# MCU.net
KiCad netlist of a schematic drawn in Altium Designer
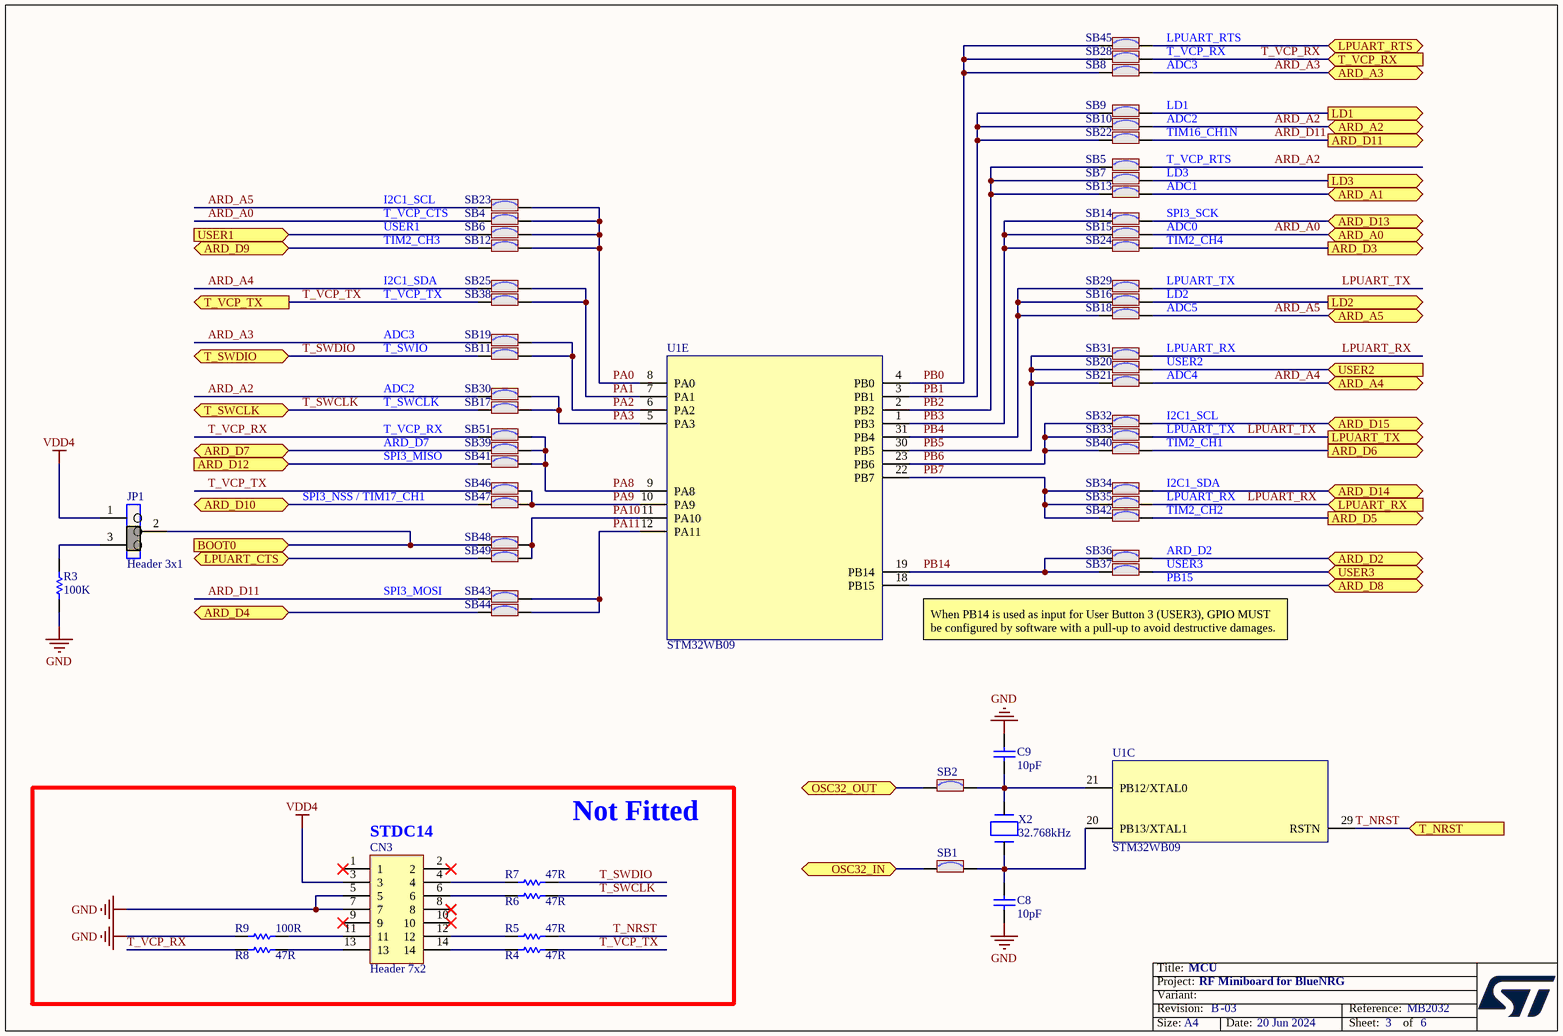
[diagram p0: MCU.SchDoc]

(export (version "E")
  (design (tool "Eeschema 10.0.6"))
  (components
    (comp (ref "C8")
      (value "10pF")
      (footprint "MCD_PARTS:C0402")
      (description "Capacitor, MLCC, 10pF, 50V, NPO, +/-5%, 0402, T=0.5mm")
      (fields (field (name "INTERNAL_PART_NUMBER") "MCD-00015") (field (name "MANUFACTURER") "YAGEO"))
      (libsource (lib "MCD_PARTS_database") (part "Capacitor"))
    )
    (comp (ref "C9")
      (value "10pF")
      (footprint "MCD_PARTS:C0402")
      (description "Capacitor, MLCC, 10pF, 50V, NPO, +/-5%, 0402, T=0.5mm")
      (fields (field (name "INTERNAL_PART_NUMBER") "MCD-00015") (field (name "MANUFACTURER") "YAGEO"))
      (libsource (lib "MCD_PARTS_database") (part "Capacitor"))
    )
    (comp (ref "CN3")
      (value "Header 7x2")
      (footprint "MCD_PARTS:CON_SAMTEC_FTSH-107-01-L-DV-K")
      (description "Header, 7x2, 1.27mm, VR, T=5.97mm, FTSH series STDC14 without Alignment Pin")
      (fields (field (name "INTERNAL_PART_NUMBER") "MCD-01531") (field (name "MANUFACTURER") "SAMTEC"))
      (libsource (lib "MCD_PARTS_database") (part "Header 7x2"))
    )
    (comp (ref "JP1")
      (value "Header 3x1")
      (footprint "CON_SAMTEC_TSW-103-07-F-S")
      (description "Header, 3x1, 2.54mm, VR, TH, T=5.84mm/2.54mm")
      (fields (field (name "INTERNAL_PART_NUMBER") "MCD-00685") (field (name "MANUFACTURER") "SAMTEC"))
      (libsource (lib "MCD_PARTS_database") (part "Jumper_Header 3x1 Fitted 2-3"))
    )
    (comp (ref "R3")
      (value "100K")
      (footprint "R0402")
      (description "Resistor, 100K, 0402, +/-1%, 1/16W")
      (fields (field (name "INTERNAL_PART_NUMBER") "MCD-00059") (field (name "MANUFACTURER") "YAGEO"))
      (libsource (lib "MCD_PARTS_database") (part "Resistor"))
    )
    (comp (ref "R4")
      (value "47R")
      (footprint "MCD_PARTS:R0402")
      (description "Resistor, 47R, 0402, +/-1%, 1/16W")
      (fields (field (name "INTERNAL_PART_NUMBER") "MCD-00481") (field (name "MANUFACTURER") "YAGEO"))
      (libsource (lib "MCD_PARTS_database") (part "Resistor"))
    )
    (comp (ref "R5")
      (value "47R")
      (footprint "MCD_PARTS:R0402")
      (description "Resistor, 47R, 0402, +/-1%, 1/16W")
      (fields (field (name "INTERNAL_PART_NUMBER") "MCD-00481") (field (name "MANUFACTURER") "YAGEO"))
      (libsource (lib "MCD_PARTS_database") (part "Resistor"))
    )
    (comp (ref "R6")
      (value "47R")
      (footprint "MCD_PARTS:R0402")
      (description "Resistor, 47R, 0402, +/-1%, 1/16W")
      (fields (field (name "INTERNAL_PART_NUMBER") "MCD-00481") (field (name "MANUFACTURER") "YAGEO"))
      (libsource (lib "MCD_PARTS_database") (part "Resistor"))
    )
    (comp (ref "R7")
      (value "47R")
      (footprint "MCD_PARTS:R0402")
      (description "Resistor, 47R, 0402, +/-1%, 1/16W")
      (fields (field (name "INTERNAL_PART_NUMBER") "MCD-00481") (field (name "MANUFACTURER") "YAGEO"))
      (libsource (lib "MCD_PARTS_database") (part "Resistor"))
    )
    (comp (ref "R8")
      (value "47R")
      (footprint "MCD_PARTS:R0402")
      (description "Resistor, 47R, 0402, +/-1%, 1/16W")
      (fields (field (name "INTERNAL_PART_NUMBER") "MCD-00481") (field (name "MANUFACTURER") "YAGEO"))
      (libsource (lib "MCD_PARTS_database") (part "Resistor"))
    )
    (comp (ref "R9")
      (value "100R")
      (footprint "MCD_PARTS:R0402")
      (description "Resistor, 100R, 0402, +/- 1%, 1/16W")
      (fields (field (name "INTERNAL_PART_NUMBER") "MCD-00067") (field (name "MANUFACTURER") "YAGEO"))
      (libsource (lib "MCD_PARTS_database") (part "Resistor"))
    )
    (comp (ref "SB1")
      (value "SB_ON")
      (footprint "MCD_PARTS:SOLDER-BRIDGE_R0402-0R")
      (description "Solder Bridge 0402 ON")
      (fields (field (name "INTERNAL_PART_NUMBER") "MCD-01618") (field (name "MANUFACTURER") "YAGEO"))
      (libsource (lib "MCD_PARTS_database") (part "SB_ON"))
    )
    (comp (ref "SB2")
      (value "SB_ON")
      (footprint "MCD_PARTS:SOLDER-BRIDGE_R0402-0R")
      (description "Solder Bridge 0402 ON")
      (fields (field (name "INTERNAL_PART_NUMBER") "MCD-01618") (field (name "MANUFACTURER") "YAGEO"))
      (libsource (lib "MCD_PARTS_database") (part "SB_ON"))
    )
    (comp (ref "SB4")
      (value "SB_ON")
      (footprint "MCD_PARTS:SOLDER-BRIDGE_R0402-0R")
      (description "Solder Bridge 0402 ON")
      (fields (field (name "INTERNAL_PART_NUMBER") "MCD-01618") (field (name "MANUFACTURER") "YAGEO"))
      (libsource (lib "MCD_PARTS_database") (part "SB_ON"))
    )
    (comp (ref "SB5")
      (value "SB_ON")
      (footprint "MCD_PARTS:SOLDER-BRIDGE_R0402-0R")
      (description "Solder Bridge 0402 ON")
      (fields (field (name "INTERNAL_PART_NUMBER") "MCD-01618") (field (name "MANUFACTURER") "YAGEO"))
      (libsource (lib "MCD_PARTS_database") (part "SB_ON"))
    )
    (comp (ref "SB6")
      (value "SB_ON")
      (footprint "MCD_PARTS:SOLDER-BRIDGE_R0402-0R")
      (description "Solder Bridge 0402 ON")
      (fields (field (name "INTERNAL_PART_NUMBER") "MCD-01618") (field (name "MANUFACTURER") "YAGEO"))
      (libsource (lib "MCD_PARTS_database") (part "SB_ON"))
    )
    (comp (ref "SB7")
      (value "SB_ON")
      (footprint "MCD_PARTS:SOLDER-BRIDGE_R0402-0R")
      (description "Solder Bridge 0402 ON")
      (fields (field (name "INTERNAL_PART_NUMBER") "MCD-01618") (field (name "MANUFACTURER") "YAGEO"))
      (libsource (lib "MCD_PARTS_database") (part "SB_ON"))
    )
    (comp (ref "SB8")
      (value "SB_ON")
      (footprint "MCD_PARTS:SOLDER-BRIDGE_R0402-0R")
      (description "Solder Bridge 0402 ON")
      (fields (field (name "INTERNAL_PART_NUMBER") "MCD-01618") (field (name "MANUFACTURER") "YAGEO"))
      (libsource (lib "MCD_PARTS_database") (part "SB_ON"))
    )
    (comp (ref "SB9")
      (value "SB_ON")
      (footprint "MCD_PARTS:SOLDER-BRIDGE_R0402-0R")
      (description "Solder Bridge 0402 ON")
      (fields (field (name "INTERNAL_PART_NUMBER") "MCD-01618") (field (name "MANUFACTURER") "YAGEO"))
      (libsource (lib "MCD_PARTS_database") (part "SB_ON"))
    )
    (comp (ref "SB10")
      (value "SB_ON")
      (footprint "MCD_PARTS:SOLDER-BRIDGE_R0402-0R")
      (description "Solder Bridge 0402 ON")
      (fields (field (name "INTERNAL_PART_NUMBER") "MCD-01618") (field (name "MANUFACTURER") "YAGEO"))
      (libsource (lib "MCD_PARTS_database") (part "SB_ON"))
    )
    (comp (ref "SB11")
      (value "SB_ON")
      (footprint "MCD_PARTS:SOLDER-BRIDGE_R0402-0R")
      (description "Solder Bridge 0402 ON")
      (fields (field (name "INTERNAL_PART_NUMBER") "MCD-01618") (field (name "MANUFACTURER") "YAGEO"))
      (libsource (lib "MCD_PARTS_database") (part "SB_ON"))
    )
    (comp (ref "SB12")
      (value "SB_ON")
      (footprint "MCD_PARTS:SOLDER-BRIDGE_R0402-0R")
      (description "Solder Bridge 0402 ON")
      (fields (field (name "INTERNAL_PART_NUMBER") "MCD-01618") (field (name "MANUFACTURER") "YAGEO"))
      (libsource (lib "MCD_PARTS_database") (part "SB_ON"))
    )
    (comp (ref "SB13")
      (value "SB_ON")
      (footprint "MCD_PARTS:SOLDER-BRIDGE_R0402-0R")
      (description "Solder Bridge 0402 ON")
      (fields (field (name "INTERNAL_PART_NUMBER") "MCD-01618") (field (name "MANUFACTURER") "YAGEO"))
      (libsource (lib "MCD_PARTS_database") (part "SB_ON"))
    )
    (comp (ref "SB14")
      (value "SB_ON")
      (footprint "MCD_PARTS:SOLDER-BRIDGE_R0402-0R")
      (description "Solder Bridge 0402 ON")
      (fields (field (name "INTERNAL_PART_NUMBER") "MCD-01618") (field (name "MANUFACTURER") "YAGEO"))
      (libsource (lib "MCD_PARTS_database") (part "SB_ON"))
    )
    (comp (ref "SB15")
      (value "SB_ON")
      (footprint "MCD_PARTS:SOLDER-BRIDGE_R0402-0R")
      (description "Solder Bridge 0402 ON")
      (fields (field (name "INTERNAL_PART_NUMBER") "MCD-01618") (field (name "MANUFACTURER") "YAGEO"))
      (libsource (lib "MCD_PARTS_database") (part "SB_ON"))
    )
    (comp (ref "SB16")
      (value "SB_ON")
      (footprint "MCD_PARTS:SOLDER-BRIDGE_R0402-0R")
      (description "Solder Bridge 0402 ON")
      (fields (field (name "INTERNAL_PART_NUMBER") "MCD-01618") (field (name "MANUFACTURER") "YAGEO"))
      (libsource (lib "MCD_PARTS_database") (part "SB_ON"))
    )
    (comp (ref "SB17")
      (value "SB_ON")
      (footprint "MCD_PARTS:SOLDER-BRIDGE_R0402-0R")
      (description "Solder Bridge 0402 ON")
      (fields (field (name "INTERNAL_PART_NUMBER") "MCD-01618") (field (name "MANUFACTURER") "YAGEO"))
      (libsource (lib "MCD_PARTS_database") (part "SB_ON"))
    )
    (comp (ref "SB18")
      (value "SB_ON")
      (footprint "MCD_PARTS:SOLDER-BRIDGE_R0402-0R")
      (description "Solder Bridge 0402 ON")
      (fields (field (name "INTERNAL_PART_NUMBER") "MCD-01618") (field (name "MANUFACTURER") "YAGEO"))
      (libsource (lib "MCD_PARTS_database") (part "SB_ON"))
    )
    (comp (ref "SB19")
      (value "SB_ON")
      (footprint "MCD_PARTS:SOLDER-BRIDGE_R0402-0R")
      (description "Solder Bridge 0402 ON")
      (fields (field (name "INTERNAL_PART_NUMBER") "MCD-01618") (field (name "MANUFACTURER") "YAGEO"))
      (libsource (lib "MCD_PARTS_database") (part "SB_ON"))
    )
    (comp (ref "SB20")
      (value "SB_ON")
      (footprint "MCD_PARTS:SOLDER-BRIDGE_R0402-0R")
      (description "Solder Bridge 0402 ON")
      (fields (field (name "INTERNAL_PART_NUMBER") "MCD-01618") (field (name "MANUFACTURER") "YAGEO"))
      (libsource (lib "MCD_PARTS_database") (part "SB_ON"))
    )
    (comp (ref "SB21")
      (value "SB_ON")
      (footprint "MCD_PARTS:SOLDER-BRIDGE_R0402-0R")
      (description "Solder Bridge 0402 ON")
      (fields (field (name "INTERNAL_PART_NUMBER") "MCD-01618") (field (name "MANUFACTURER") "YAGEO"))
      (libsource (lib "MCD_PARTS_database") (part "SB_ON"))
    )
    (comp (ref "SB22")
      (value "SB_ON")
      (footprint "MCD_PARTS:SOLDER-BRIDGE_R0402-0R")
      (description "Solder Bridge 0402 ON")
      (fields (field (name "INTERNAL_PART_NUMBER") "MCD-01618") (field (name "MANUFACTURER") "YAGEO"))
      (libsource (lib "MCD_PARTS_database") (part "SB_ON"))
    )
    (comp (ref "SB23")
      (value "SB_ON")
      (footprint "MCD_PARTS:SOLDER-BRIDGE_R0402-0R")
      (description "Solder Bridge 0402 ON")
      (fields (field (name "INTERNAL_PART_NUMBER") "MCD-01618") (field (name "MANUFACTURER") "YAGEO"))
      (libsource (lib "MCD_PARTS_database") (part "SB_ON"))
    )
    (comp (ref "SB24")
      (value "SB_ON")
      (footprint "MCD_PARTS:SOLDER-BRIDGE_R0402-0R")
      (description "Solder Bridge 0402 ON")
      (fields (field (name "INTERNAL_PART_NUMBER") "MCD-01618") (field (name "MANUFACTURER") "YAGEO"))
      (libsource (lib "MCD_PARTS_database") (part "SB_ON"))
    )
    (comp (ref "SB25")
      (value "SB_ON")
      (footprint "MCD_PARTS:SOLDER-BRIDGE_R0402-0R")
      (description "Solder Bridge 0402 ON")
      (fields (field (name "INTERNAL_PART_NUMBER") "MCD-01618") (field (name "MANUFACTURER") "YAGEO"))
      (libsource (lib "MCD_PARTS_database") (part "SB_ON"))
    )
    (comp (ref "SB28")
      (value "SB_ON")
      (footprint "MCD_PARTS:SOLDER-BRIDGE_R0402-0R")
      (description "Solder Bridge 0402 ON")
      (fields (field (name "INTERNAL_PART_NUMBER") "MCD-01618") (field (name "MANUFACTURER") "YAGEO"))
      (libsource (lib "MCD_PARTS_database") (part "SB_ON"))
    )
    (comp (ref "SB29")
      (value "SB_ON")
      (footprint "MCD_PARTS:SOLDER-BRIDGE_R0402-0R")
      (description "Solder Bridge 0402 ON")
      (fields (field (name "INTERNAL_PART_NUMBER") "MCD-01618") (field (name "MANUFACTURER") "YAGEO"))
      (libsource (lib "MCD_PARTS_database") (part "SB_ON"))
    )
    (comp (ref "SB30")
      (value "SB_ON")
      (footprint "MCD_PARTS:SOLDER-BRIDGE_R0402-0R")
      (description "Solder Bridge 0402 ON")
      (fields (field (name "INTERNAL_PART_NUMBER") "MCD-01618") (field (name "MANUFACTURER") "YAGEO"))
      (libsource (lib "MCD_PARTS_database") (part "SB_ON"))
    )
    (comp (ref "SB31")
      (value "SB_ON")
      (footprint "MCD_PARTS:SOLDER-BRIDGE_R0402-0R")
      (description "Solder Bridge 0402 ON")
      (fields (field (name "INTERNAL_PART_NUMBER") "MCD-01618") (field (name "MANUFACTURER") "YAGEO"))
      (libsource (lib "MCD_PARTS_database") (part "SB_ON"))
    )
    (comp (ref "SB32")
      (value "SB_ON")
      (footprint "MCD_PARTS:SOLDER-BRIDGE_R0402-0R")
      (description "Solder Bridge 0402 ON")
      (fields (field (name "INTERNAL_PART_NUMBER") "MCD-01618") (field (name "MANUFACTURER") "YAGEO"))
      (libsource (lib "MCD_PARTS_database") (part "SB_ON"))
    )
    (comp (ref "SB33")
      (value "SB_ON")
      (footprint "MCD_PARTS:SOLDER-BRIDGE_R0402-0R")
      (description "Solder Bridge 0402 ON")
      (fields (field (name "INTERNAL_PART_NUMBER") "MCD-01618") (field (name "MANUFACTURER") "YAGEO"))
      (libsource (lib "MCD_PARTS_database") (part "SB_ON"))
    )
    (comp (ref "SB34")
      (value "SB_ON")
      (footprint "MCD_PARTS:SOLDER-BRIDGE_R0402-0R")
      (description "Solder Bridge 0402 ON")
      (fields (field (name "INTERNAL_PART_NUMBER") "MCD-01618") (field (name "MANUFACTURER") "YAGEO"))
      (libsource (lib "MCD_PARTS_database") (part "SB_ON"))
    )
    (comp (ref "SB35")
      (value "SB_ON")
      (footprint "MCD_PARTS:SOLDER-BRIDGE_R0402-0R")
      (description "Solder Bridge 0402 ON")
      (fields (field (name "INTERNAL_PART_NUMBER") "MCD-01618") (field (name "MANUFACTURER") "YAGEO"))
      (libsource (lib "MCD_PARTS_database") (part "SB_ON"))
    )
    (comp (ref "SB36")
      (value "SB_ON")
      (footprint "MCD_PARTS:SOLDER-BRIDGE_R0402-0R")
      (description "Solder Bridge 0402 ON")
      (fields (field (name "INTERNAL_PART_NUMBER") "MCD-01618") (field (name "MANUFACTURER") "YAGEO"))
      (libsource (lib "MCD_PARTS_database") (part "SB_ON"))
    )
    (comp (ref "SB37")
      (value "SB_ON")
      (footprint "MCD_PARTS:SOLDER-BRIDGE_R0402-0R")
      (description "Solder Bridge 0402 ON")
      (fields (field (name "INTERNAL_PART_NUMBER") "MCD-01618") (field (name "MANUFACTURER") "YAGEO"))
      (libsource (lib "MCD_PARTS_database") (part "SB_ON"))
    )
    (comp (ref "SB38")
      (value "SB_ON")
      (footprint "MCD_PARTS:SOLDER-BRIDGE_R0402-0R")
      (description "Solder Bridge 0402 ON")
      (fields (field (name "INTERNAL_PART_NUMBER") "MCD-01618") (field (name "MANUFACTURER") "YAGEO"))
      (libsource (lib "MCD_PARTS_database") (part "SB_ON"))
    )
    (comp (ref "SB39")
      (value "SB_ON")
      (footprint "MCD_PARTS:SOLDER-BRIDGE_R0402-0R")
      (description "Solder Bridge 0402 ON")
      (fields (field (name "INTERNAL_PART_NUMBER") "MCD-01618") (field (name "MANUFACTURER") "YAGEO"))
      (libsource (lib "MCD_PARTS_database") (part "SB_ON"))
    )
    (comp (ref "SB40")
      (value "SB_ON")
      (footprint "MCD_PARTS:SOLDER-BRIDGE_R0402-0R")
      (description "Solder Bridge 0402 ON")
      (fields (field (name "INTERNAL_PART_NUMBER") "MCD-01618") (field (name "MANUFACTURER") "YAGEO"))
      (libsource (lib "MCD_PARTS_database") (part "SB_ON"))
    )
    (comp (ref "SB41")
      (value "SB_ON")
      (footprint "MCD_PARTS:SOLDER-BRIDGE_R0402-0R")
      (description "Solder Bridge 0402 ON")
      (fields (field (name "INTERNAL_PART_NUMBER") "MCD-01618") (field (name "MANUFACTURER") "YAGEO"))
      (libsource (lib "MCD_PARTS_database") (part "SB_ON"))
    )
    (comp (ref "SB42")
      (value "SB_ON")
      (footprint "MCD_PARTS:SOLDER-BRIDGE_R0402-0R")
      (description "Solder Bridge 0402 ON")
      (fields (field (name "INTERNAL_PART_NUMBER") "MCD-01618") (field (name "MANUFACTURER") "YAGEO"))
      (libsource (lib "MCD_PARTS_database") (part "SB_ON"))
    )
    (comp (ref "SB43")
      (value "SB_ON")
      (footprint "MCD_PARTS:SOLDER-BRIDGE_R0402-0R")
      (description "Solder Bridge 0402 ON")
      (fields (field (name "INTERNAL_PART_NUMBER") "MCD-01618") (field (name "MANUFACTURER") "YAGEO"))
      (libsource (lib "MCD_PARTS_database") (part "SB_ON"))
    )
    (comp (ref "SB44")
      (value "SB_ON")
      (footprint "MCD_PARTS:SOLDER-BRIDGE_R0402-0R")
      (description "Solder Bridge 0402 ON")
      (fields (field (name "INTERNAL_PART_NUMBER") "MCD-01618") (field (name "MANUFACTURER") "YAGEO"))
      (libsource (lib "MCD_PARTS_database") (part "SB_ON"))
    )
    (comp (ref "SB45")
      (value "SB_ON")
      (footprint "MCD_PARTS:SOLDER-BRIDGE_R0402-0R")
      (description "Solder Bridge 0402 ON")
      (fields (field (name "INTERNAL_PART_NUMBER") "MCD-01618") (field (name "MANUFACTURER") "YAGEO"))
      (libsource (lib "MCD_PARTS_database") (part "SB_ON"))
    )
    (comp (ref "SB46")
      (value "SB_ON")
      (footprint "MCD_PARTS:SOLDER-BRIDGE_R0402-0R")
      (description "Solder Bridge 0402 ON")
      (fields (field (name "INTERNAL_PART_NUMBER") "MCD-01618") (field (name "MANUFACTURER") "YAGEO"))
      (libsource (lib "MCD_PARTS_database") (part "SB_ON"))
    )
    (comp (ref "SB47")
      (value "SB_ON")
      (footprint "MCD_PARTS:SOLDER-BRIDGE_R0402-0R")
      (description "Solder Bridge 0402 ON")
      (fields (field (name "INTERNAL_PART_NUMBER") "MCD-01618") (field (name "MANUFACTURER") "YAGEO"))
      (libsource (lib "MCD_PARTS_database") (part "SB_ON"))
    )
    (comp (ref "SB48")
      (value "SB_ON")
      (footprint "MCD_PARTS:SOLDER-BRIDGE_R0402-0R")
      (description "Solder Bridge 0402 ON")
      (fields (field (name "INTERNAL_PART_NUMBER") "MCD-01618") (field (name "MANUFACTURER") "YAGEO"))
      (libsource (lib "MCD_PARTS_database") (part "SB_ON"))
    )
    (comp (ref "SB49")
      (value "SB_ON")
      (footprint "MCD_PARTS:SOLDER-BRIDGE_R0402-0R")
      (description "Solder Bridge 0402 ON")
      (fields (field (name "INTERNAL_PART_NUMBER") "MCD-01618") (field (name "MANUFACTURER") "YAGEO"))
      (libsource (lib "MCD_PARTS_database") (part "SB_ON"))
    )
    (comp (ref "SB51")
      (value "SB_ON")
      (footprint "MCD_PARTS:SOLDER-BRIDGE_R0402-0R")
      (description "Solder Bridge 0402 ON")
      (fields (field (name "INTERNAL_PART_NUMBER") "MCD-01618") (field (name "MANUFACTURER") "YAGEO"))
      (libsource (lib "") (part "SB_ON_1"))
    )
    (comp (ref "U1")
      (value "STM32WB09")
      (footprint "ICC_QFN32-EPAD_5X5_P050")
      (description "Bluetooth® Low Energy wireless SoC")
      (fields
        (field (name "INTERNAL_PART_NUMBER") "MCD-03444")
        (field (name "MANUFACTURER") "STMICROELECTRONICS")
      )
      (libsource (lib "MCD_PARTS_database") (part "STM32WB09"))
    )
    (comp (ref "X2")
      (value "32.768kHz")
      (footprint "MCD_PARTS:CRY_NX2012SA_2P")
      (description "Crystal, 32.768kHz, 7pF, +/-20ppm, 80K, 2.05x1.2mm")
      (fields (field (name "INTERNAL_PART_NUMBER") "MCD-01445") (field (name "BMS_PART_NUMBER") "9157043"))
      (libsource (lib "MCD_PARTS_database") (part "XTAL_2_PINS"))
    )
  )
  (nets
    (net (code "1") (name "/ARD_A0") (class "Default")
      (node (ref "SB15") (pin "2") (pinfunction "2_2") (pintype "passive"))
      (node (ref "SB4") (pin "1") (pinfunction "1_1") (pintype "passive"))
    )
    (net (code "2") (name "/ARD_A1") (class "Default")
      (node (ref "SB13") (pin "2") (pinfunction "2_2") (pintype "passive"))
    )
    (net (code "3") (name "/ARD_A2") (class "Default")
      (node (ref "SB10") (pin "2") (pinfunction "2_2") (pintype "passive"))
      (node (ref "SB30") (pin "1") (pinfunction "1_1") (pintype "passive"))
      (node (ref "SB5") (pin "2") (pinfunction "2_2") (pintype "passive"))
    )
    (net (code "4") (name "/ARD_A3") (class "Default")
      (node (ref "SB19") (pin "1") (pinfunction "1_1") (pintype "passive"))
      (node (ref "SB8") (pin "2") (pinfunction "2_2") (pintype "passive"))
    )
    (net (code "5") (name "/ARD_A4") (class "Default")
      (node (ref "SB21") (pin "2") (pinfunction "2_2") (pintype "passive"))
      (node (ref "SB25") (pin "1") (pinfunction "1_1") (pintype "passive"))
    )
    (net (code "6") (name "/ARD_A5") (class "Default")
      (node (ref "SB18") (pin "2") (pinfunction "2_2") (pintype "passive"))
      (node (ref "SB23") (pin "1") (pinfunction "1_1") (pintype "passive"))
    )
    (net (code "7") (name "/ARD_D2") (class "Default")
      (node (ref "SB36") (pin "2") (pinfunction "2_2") (pintype "passive"))
    )
    (net (code "8") (name "/ARD_D3") (class "Default")
      (node (ref "SB24") (pin "2") (pinfunction "2_2") (pintype "passive"))
    )
    (net (code "9") (name "/ARD_D4") (class "Default")
      (node (ref "SB44") (pin "1") (pinfunction "1_1") (pintype "passive"))
    )
    (net (code "10") (name "/ARD_D5") (class "Default")
      (node (ref "SB42") (pin "2") (pinfunction "2_2") (pintype "passive"))
    )
    (net (code "11") (name "/ARD_D6") (class "Default")
      (node (ref "SB40") (pin "2") (pinfunction "2_2") (pintype "passive"))
    )
    (net (code "12") (name "/ARD_D7") (class "Default")
      (node (ref "SB39") (pin "1") (pinfunction "1_1") (pintype "passive"))
    )
    (net (code "13") (name "/ARD_D8") (class "Default")
      (node (ref "U1") (pin "18") (pinfunction "PB15_18") (pintype "passive"))
    )
    (net (code "14") (name "/ARD_D9") (class "Default")
      (node (ref "SB12") (pin "1") (pinfunction "1_1") (pintype "passive"))
    )
    (net (code "15") (name "/ARD_D10") (class "Default")
      (node (ref "SB47") (pin "1") (pinfunction "1_1") (pintype "passive"))
    )
    (net (code "16") (name "/ARD_D11") (class "Default")
      (node (ref "SB22") (pin "2") (pinfunction "2_2") (pintype "passive"))
      (node (ref "SB43") (pin "1") (pinfunction "1_1") (pintype "passive"))
    )
    (net (code "17") (name "/ARD_D12") (class "Default")
      (node (ref "SB41") (pin "1") (pinfunction "1_1") (pintype "passive"))
    )
    (net (code "18") (name "/ARD_D13") (class "Default")
      (node (ref "SB14") (pin "2") (pinfunction "2_2") (pintype "passive"))
    )
    (net (code "19") (name "/ARD_D14") (class "Default")
      (node (ref "SB34") (pin "2") (pinfunction "2_2") (pintype "passive"))
    )
    (net (code "20") (name "/ARD_D15") (class "Default")
      (node (ref "SB32") (pin "2") (pinfunction "2_2") (pintype "passive"))
    )
    (net (code "21") (name "/BOOT0") (class "Default")
      (node (ref "JP1") (pin "2") (pinfunction "2_2") (pintype "passive"))
      (node (ref "SB48") (pin "1") (pinfunction "1_1") (pintype "passive"))
    )
    (net (code "22") (name "/LD1") (class "Default")
      (node (ref "SB9") (pin "2") (pinfunction "2_2") (pintype "passive"))
    )
    (net (code "23") (name "/LD2") (class "Default")
      (node (ref "SB16") (pin "2") (pinfunction "2_2") (pintype "passive"))
    )
    (net (code "24") (name "/LD3") (class "Default")
      (node (ref "SB7") (pin "2") (pinfunction "2_2") (pintype "passive"))
    )
    (net (code "25") (name "/LPUART_CTS") (class "Default")
      (node (ref "SB49") (pin "1") (pinfunction "1_1") (pintype "passive"))
    )
    (net (code "26") (name "/LPUART_RTS") (class "Default")
      (node (ref "SB45") (pin "2") (pinfunction "2_2") (pintype "passive"))
    )
    (net (code "27") (name "/LPUART_RX") (class "Default")
      (node (ref "SB31") (pin "2") (pinfunction "2_2") (pintype "passive"))
      (node (ref "SB35") (pin "2") (pinfunction "2_2") (pintype "passive"))
    )
    (net (code "28") (name "/LPUART_TX") (class "Default")
      (node (ref "SB29") (pin "2") (pinfunction "2_2") (pintype "passive"))
      (node (ref "SB33") (pin "2") (pinfunction "2_2") (pintype "passive"))
    )
    (net (code "29") (name "/OSC32_IN") (class "Default")
      (node (ref "SB1") (pin "1") (pinfunction "1_1") (pintype "passive"))
    )
    (net (code "30") (name "/OSC32_OUT") (class "Default")
      (node (ref "SB2") (pin "1") (pinfunction "1_1") (pintype "passive"))
    )
    (net (code "31") (name "/PA0") (class "Default")
      (node (ref "SB12") (pin "2") (pinfunction "2_2") (pintype "passive"))
      (node (ref "SB23") (pin "2") (pinfunction "2_2") (pintype "passive"))
      (node (ref "SB4") (pin "2") (pinfunction "2_2") (pintype "passive"))
      (node (ref "SB6") (pin "2") (pinfunction "2_2") (pintype "passive"))
      (node (ref "U1") (pin "8") (pinfunction "PA0_8") (pintype "passive"))
    )
    (net (code "32") (name "/PA1") (class "Default")
      (node (ref "SB25") (pin "2") (pinfunction "2_2") (pintype "passive"))
      (node (ref "SB38") (pin "2") (pinfunction "2_2") (pintype "passive"))
      (node (ref "U1") (pin "7") (pinfunction "PA1_7") (pintype "passive"))
    )
    (net (code "33") (name "/PA2") (class "Default")
      (node (ref "SB11") (pin "2") (pinfunction "2_2") (pintype "passive"))
      (node (ref "SB19") (pin "2") (pinfunction "2_2") (pintype "passive"))
      (node (ref "U1") (pin "6") (pinfunction "PA2_6") (pintype "passive"))
    )
    (net (code "34") (name "/PA3") (class "Default")
      (node (ref "SB17") (pin "2") (pinfunction "2_2") (pintype "passive"))
      (node (ref "SB30") (pin "2") (pinfunction "2_2") (pintype "passive"))
      (node (ref "U1") (pin "5") (pinfunction "PA3_5") (pintype "passive"))
    )
    (net (code "35") (name "/PA8") (class "Default")
      (node (ref "SB39") (pin "2") (pinfunction "2_2") (pintype "passive"))
      (node (ref "SB41") (pin "2") (pinfunction "2_2") (pintype "passive"))
      (node (ref "SB51") (pin "1") (pinfunction "1_1") (pintype "passive"))
      (node (ref "U1") (pin "9") (pinfunction "PA8_9") (pintype "passive"))
    )
    (net (code "36") (name "/PA9") (class "Default")
      (node (ref "SB46") (pin "2") (pinfunction "2_2") (pintype "passive"))
      (node (ref "SB47") (pin "2") (pinfunction "2_2") (pintype "passive"))
      (node (ref "U1") (pin "10") (pinfunction "PA9_10") (pintype "passive"))
    )
    (net (code "37") (name "/PA10") (class "Default")
      (node (ref "SB48") (pin "2") (pinfunction "2_2") (pintype "passive"))
      (node (ref "SB49") (pin "2") (pinfunction "2_2") (pintype "passive"))
      (node (ref "U1") (pin "11") (pinfunction "PA10_11") (pintype "passive"))
    )
    (net (code "38") (name "/PA11") (class "Default")
      (node (ref "SB43") (pin "2") (pinfunction "2_2") (pintype "passive"))
      (node (ref "SB44") (pin "2") (pinfunction "2_2") (pintype "passive"))
      (node (ref "U1") (pin "12") (pinfunction "PA11_12") (pintype "passive"))
    )
    (net (code "39") (name "/PB0") (class "Default")
      (node (ref "SB28") (pin "1") (pinfunction "1_1") (pintype "passive"))
      (node (ref "SB45") (pin "1") (pinfunction "1_1") (pintype "passive"))
      (node (ref "SB8") (pin "1") (pinfunction "1_1") (pintype "passive"))
      (node (ref "U1") (pin "4") (pinfunction "PB0_4") (pintype "passive"))
    )
    (net (code "40") (name "/PB1") (class "Default")
      (node (ref "SB10") (pin "1") (pinfunction "1_1") (pintype "passive"))
      (node (ref "SB22") (pin "1") (pinfunction "1_1") (pintype "passive"))
      (node (ref "SB9") (pin "1") (pinfunction "1_1") (pintype "passive"))
      (node (ref "U1") (pin "3") (pinfunction "PB1_3") (pintype "passive"))
    )
    (net (code "41") (name "/PB2") (class "Default")
      (node (ref "SB13") (pin "1") (pinfunction "1_1") (pintype "passive"))
      (node (ref "SB5") (pin "1") (pinfunction "1_1") (pintype "passive"))
      (node (ref "SB7") (pin "1") (pinfunction "1_1") (pintype "passive"))
      (node (ref "U1") (pin "2") (pinfunction "PB2_2") (pintype "passive"))
    )
    (net (code "42") (name "/PB3") (class "Default")
      (node (ref "SB14") (pin "1") (pinfunction "1_1") (pintype "passive"))
      (node (ref "SB15") (pin "1") (pinfunction "1_1") (pintype "passive"))
      (node (ref "SB24") (pin "1") (pinfunction "1_1") (pintype "passive"))
      (node (ref "U1") (pin "1") (pinfunction "PB3_1") (pintype "passive"))
    )
    (net (code "43") (name "/PB4") (class "Default")
      (node (ref "SB16") (pin "1") (pinfunction "1_1") (pintype "passive"))
      (node (ref "SB18") (pin "1") (pinfunction "1_1") (pintype "passive"))
      (node (ref "SB29") (pin "1") (pinfunction "1_1") (pintype "passive"))
      (node (ref "U1") (pin "31") (pinfunction "PB4_31") (pintype "passive"))
    )
    (net (code "44") (name "/PB5") (class "Default")
      (node (ref "SB20") (pin "1") (pinfunction "1_1") (pintype "passive"))
      (node (ref "SB21") (pin "1") (pinfunction "1_1") (pintype "passive"))
      (node (ref "SB31") (pin "1") (pinfunction "1_1") (pintype "passive"))
      (node (ref "U1") (pin "30") (pinfunction "PB5_30") (pintype "passive"))
    )
    (net (code "45") (name "/PB6") (class "Default")
      (node (ref "SB32") (pin "1") (pinfunction "1_1") (pintype "passive"))
      (node (ref "SB33") (pin "1") (pinfunction "1_1") (pintype "passive"))
      (node (ref "SB40") (pin "1") (pinfunction "1_1") (pintype "passive"))
      (node (ref "U1") (pin "23") (pinfunction "PB6_23") (pintype "passive"))
    )
    (net (code "46") (name "/PB7") (class "Default")
      (node (ref "SB34") (pin "1") (pinfunction "1_1") (pintype "passive"))
      (node (ref "SB35") (pin "1") (pinfunction "1_1") (pintype "passive"))
      (node (ref "SB42") (pin "1") (pinfunction "1_1") (pintype "passive"))
      (node (ref "U1") (pin "22") (pinfunction "PB7_22") (pintype "passive"))
    )
    (net (code "47") (name "/PB14") (class "Default")
      (node (ref "SB36") (pin "1") (pinfunction "1_1") (pintype "passive"))
      (node (ref "SB37") (pin "1") (pinfunction "1_1") (pintype "passive"))
      (node (ref "U1") (pin "19") (pinfunction "PB14_19") (pintype "passive"))
    )
    (net (code "48") (name "/T_NRST") (class "Default")
      (node (ref "R5") (pin "2") (pinfunction "2_2") (pintype "passive"))
      (node (ref "U1") (pin "29") (pinfunction "RSTN_29") (pintype "passive"))
    )
    (net (code "49") (name "/T_SWCLK") (class "Default")
      (node (ref "R6") (pin "2") (pinfunction "2_2") (pintype "passive"))
      (node (ref "SB17") (pin "1") (pinfunction "1_1") (pintype "passive"))
    )
    (net (code "50") (name "/T_SWDIO") (class "Default")
      (node (ref "R7") (pin "2") (pinfunction "2_2") (pintype "passive"))
      (node (ref "SB11") (pin "1") (pinfunction "1_1") (pintype "passive"))
    )
    (net (code "51") (name "/T_VCP_RX") (class "Default")
      (node (ref "R8") (pin "1") (pinfunction "1_1") (pintype "passive"))
      (node (ref "SB28") (pin "2") (pinfunction "2_2") (pintype "passive"))
      (node (ref "SB51") (pin "2") (pinfunction "2_2") (pintype "passive"))
    )
    (net (code "52") (name "/T_VCP_TX") (class "Default")
      (node (ref "R4") (pin "2") (pinfunction "2_2") (pintype "passive"))
      (node (ref "SB38") (pin "1") (pinfunction "1_1") (pintype "passive"))
      (node (ref "SB46") (pin "1") (pinfunction "1_1") (pintype "passive"))
    )
    (net (code "53") (name "/USER1") (class "Default")
      (node (ref "SB6") (pin "1") (pinfunction "1_1") (pintype "passive"))
    )
    (net (code "54") (name "/USER2") (class "Default")
      (node (ref "SB20") (pin "2") (pinfunction "2_2") (pintype "passive"))
    )
    (net (code "55") (name "/USER3") (class "Default")
      (node (ref "SB37") (pin "2") (pinfunction "2_2") (pintype "passive"))
    )
    (net (code "56") (name "GND") (class "Default")
      (node (ref "C8") (pin "1") (pinfunction "1_1") (pintype "passive"))
      (node (ref "C9") (pin "2") (pinfunction "2_2") (pintype "passive"))
      (node (ref "CN3") (pin "5") (pinfunction "5_5") (pintype "passive"))
      (node (ref "CN3") (pin "7") (pinfunction "7_7") (pintype "passive"))
      (node (ref "R3") (pin "1") (pinfunction "1_1") (pintype "passive"))
      (node (ref "R9") (pin "1") (pinfunction "1_1") (pintype "passive"))
    )
    (net (code "57") (name "Net-(CN3-Pad4)") (class "Default")
      (node (ref "CN3") (pin "4") (pinfunction "4_4") (pintype "passive"))
      (node (ref "R7") (pin "1") (pinfunction "1_1") (pintype "passive"))
    )
    (net (code "58") (name "Net-(CN3-Pad6)") (class "Default")
      (node (ref "CN3") (pin "6") (pinfunction "6_6") (pintype "passive"))
      (node (ref "R6") (pin "1") (pinfunction "1_1") (pintype "passive"))
    )
    (net (code "59") (name "Net-(CN3-Pad11)") (class "Default")
      (node (ref "CN3") (pin "11") (pinfunction "11_11") (pintype "passive"))
      (node (ref "R9") (pin "2") (pinfunction "2_2") (pintype "passive"))
    )
    (net (code "60") (name "Net-(CN3-Pad12)") (class "Default")
      (node (ref "CN3") (pin "12") (pinfunction "12_12") (pintype "passive"))
      (node (ref "R5") (pin "1") (pinfunction "1_1") (pintype "passive"))
    )
    (net (code "61") (name "Net-(CN3-Pad13)") (class "Default")
      (node (ref "CN3") (pin "13") (pinfunction "13_13") (pintype "passive"))
      (node (ref "R8") (pin "2") (pinfunction "2_2") (pintype "passive"))
    )
    (net (code "62") (name "Net-(CN3-Pad14)") (class "Default")
      (node (ref "CN3") (pin "14") (pinfunction "14_14") (pintype "passive"))
      (node (ref "R4") (pin "1") (pinfunction "1_1") (pintype "passive"))
    )
    (net (code "63") (name "Net-(JP1-Pad3)") (class "Default")
      (node (ref "JP1") (pin "3") (pinfunction "3_3") (pintype "passive"))
      (node (ref "R3") (pin "2") (pinfunction "2_2") (pintype "passive"))
    )
    (net (code "64") (name "Net-(U1C-PB12{slash}XTAL0)") (class "Default")
      (node (ref "C9") (pin "1") (pinfunction "1_1") (pintype "passive"))
      (node (ref "SB2") (pin "2") (pinfunction "2_2") (pintype "passive"))
      (node (ref "U1") (pin "21") (pinfunction "PB12/XTAL0_21") (pintype "passive"))
      (node (ref "X2") (pin "1") (pinfunction "X1_1") (pintype "passive"))
    )
    (net (code "65") (name "Net-(U1C-PB13{slash}XTAL1)") (class "Default")
      (node (ref "C8") (pin "2") (pinfunction "2_2") (pintype "passive"))
      (node (ref "SB1") (pin "2") (pinfunction "2_2") (pintype "passive"))
      (node (ref "U1") (pin "20") (pinfunction "PB13/XTAL1_20") (pintype "passive"))
      (node (ref "X2") (pin "2") (pinfunction "X2_2") (pintype "passive"))
    )
    (net (code "66") (name "VDD4") (class "Default")
      (node (ref "CN3") (pin "3") (pinfunction "3_3") (pintype "passive"))
      (node (ref "JP1") (pin "1") (pinfunction "1_1") (pintype "passive"))
    )
    (net (code "67") (name "unconnected-(CN3-Pad1)") (class "Default")
      (node (ref "CN3") (pin "1") (pinfunction "1_1") (pintype "passive+no_connect"))
    )
    (net (code "68") (name "unconnected-(CN3-Pad2)") (class "Default")
      (node (ref "CN3") (pin "2") (pinfunction "2_2") (pintype "passive+no_connect"))
    )
    (net (code "69") (name "unconnected-(CN3-Pad8)") (class "Default")
      (node (ref "CN3") (pin "8") (pinfunction "8_8") (pintype "passive+no_connect"))
    )
    (net (code "70") (name "unconnected-(CN3-Pad9)") (class "Default")
      (node (ref "CN3") (pin "9") (pinfunction "9_9") (pintype "passive+no_connect"))
    )
    (net (code "71") (name "unconnected-(CN3-Pad10)") (class "Default")
      (node (ref "CN3") (pin "10") (pinfunction "10_10") (pintype "passive+no_connect"))
    )
  )
)
